# PROIECT_OPEN_READER_v56.net
KiCad netlist of a schematic drawn in EAGLE
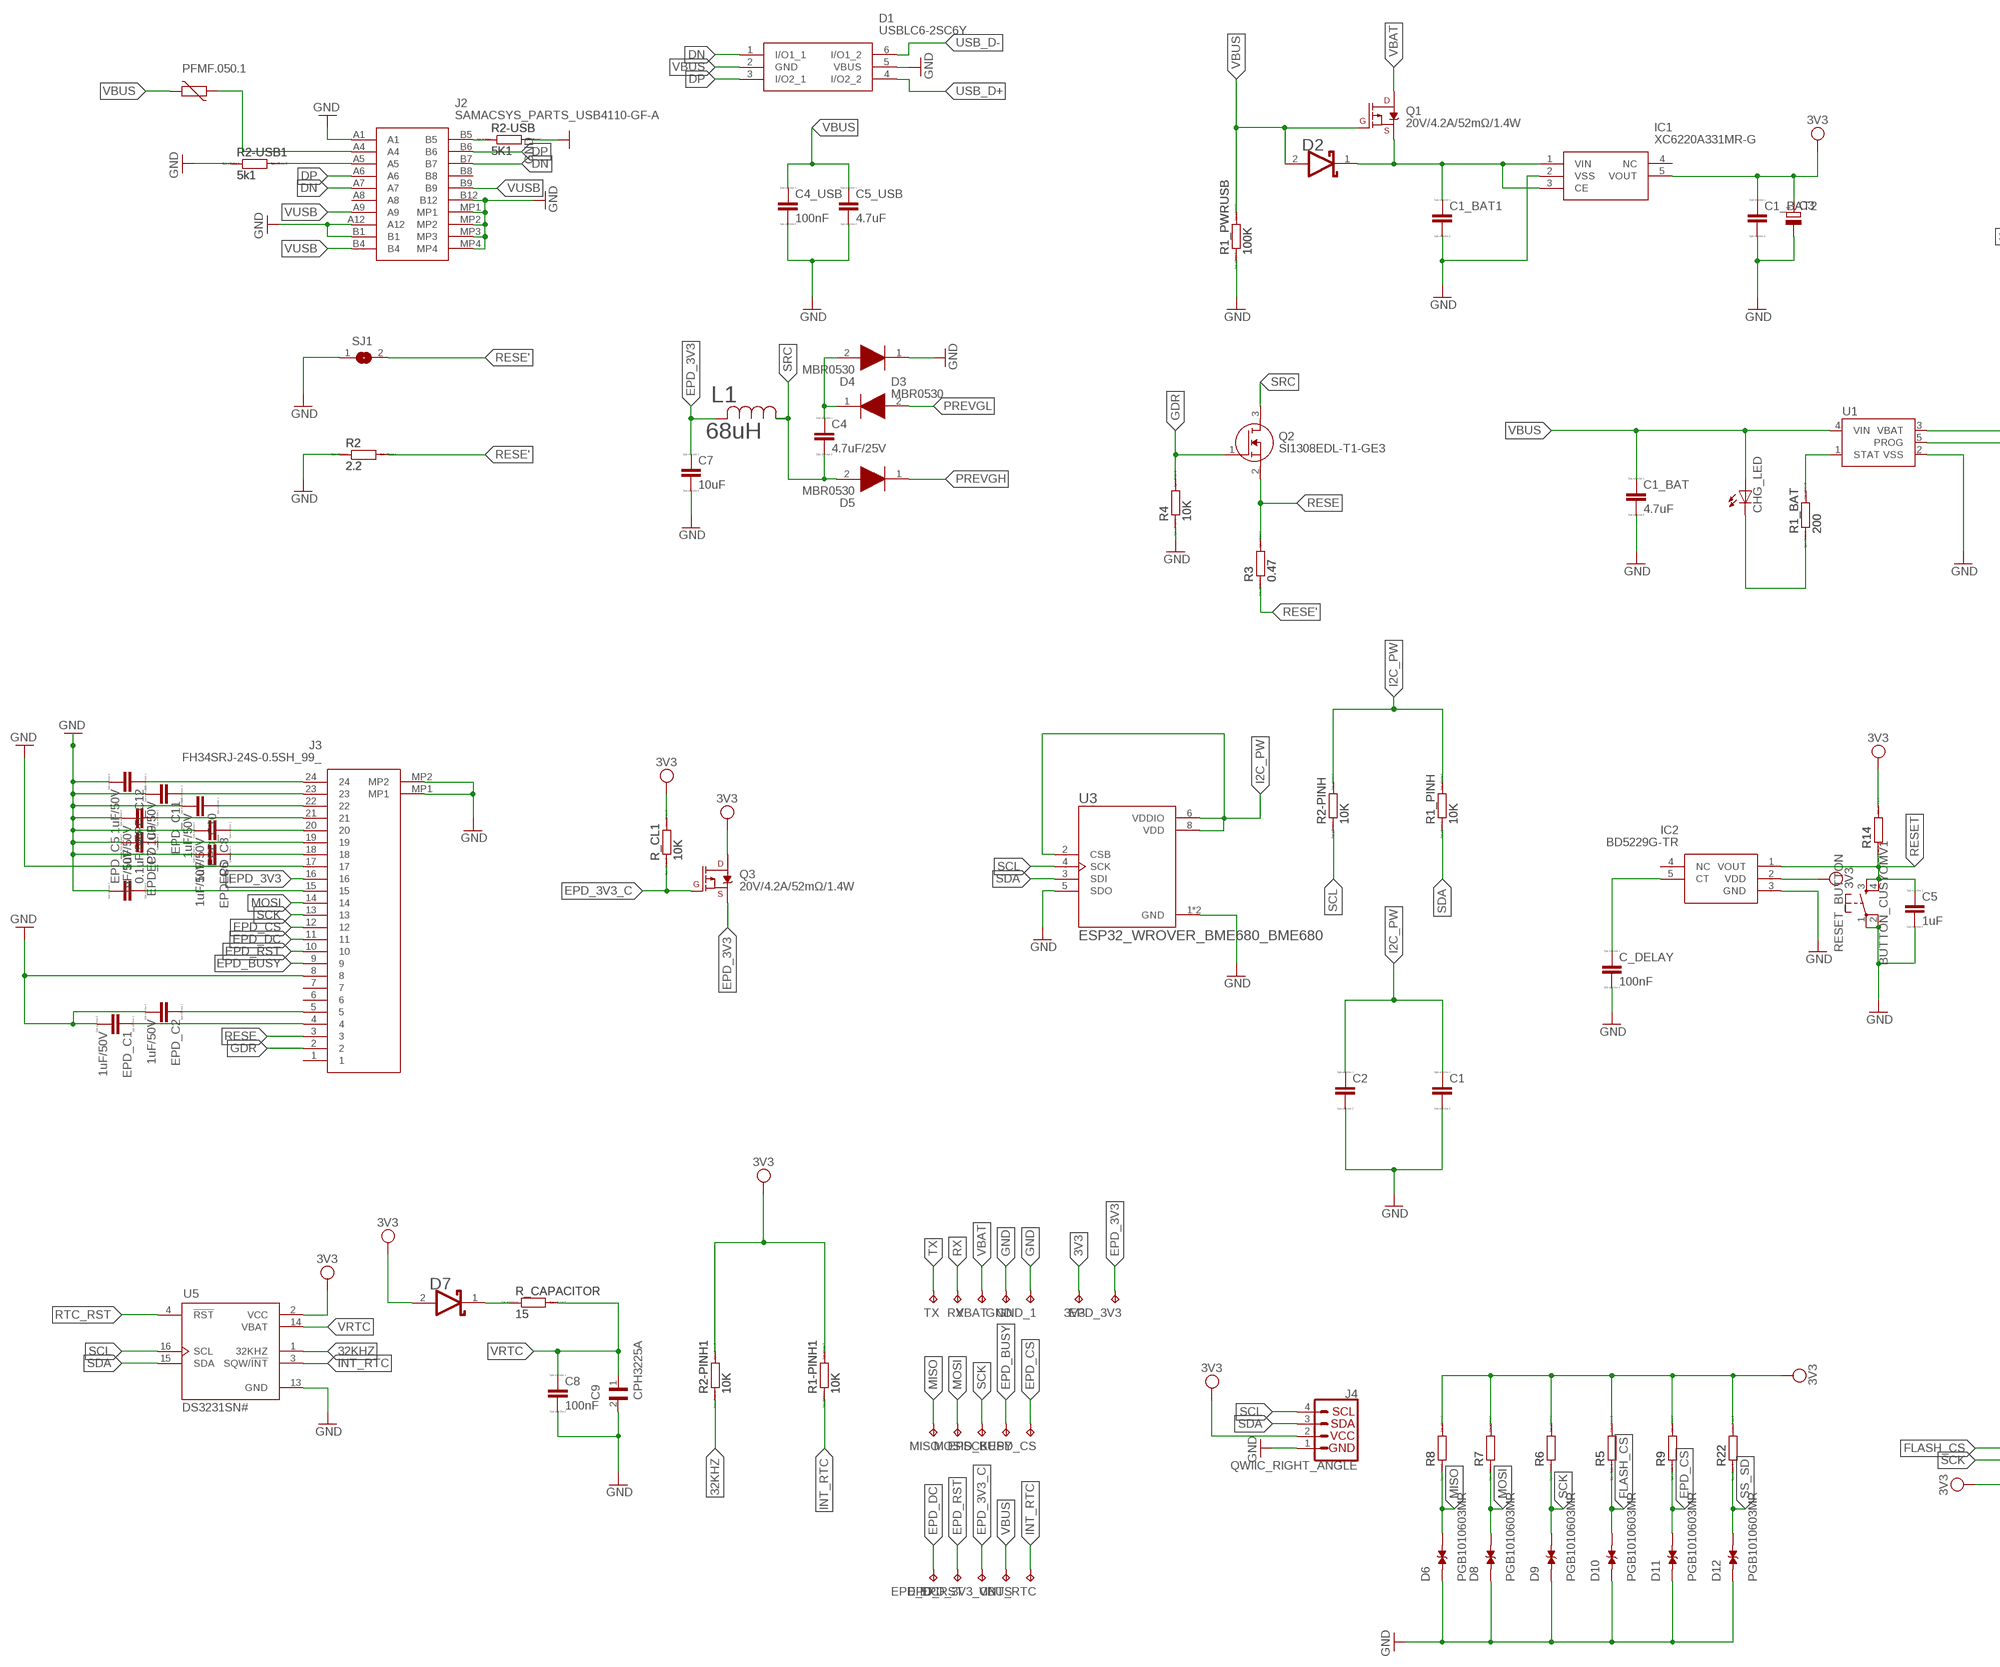
[diagram p0: schematic, sheet 1, part 1 of 2]
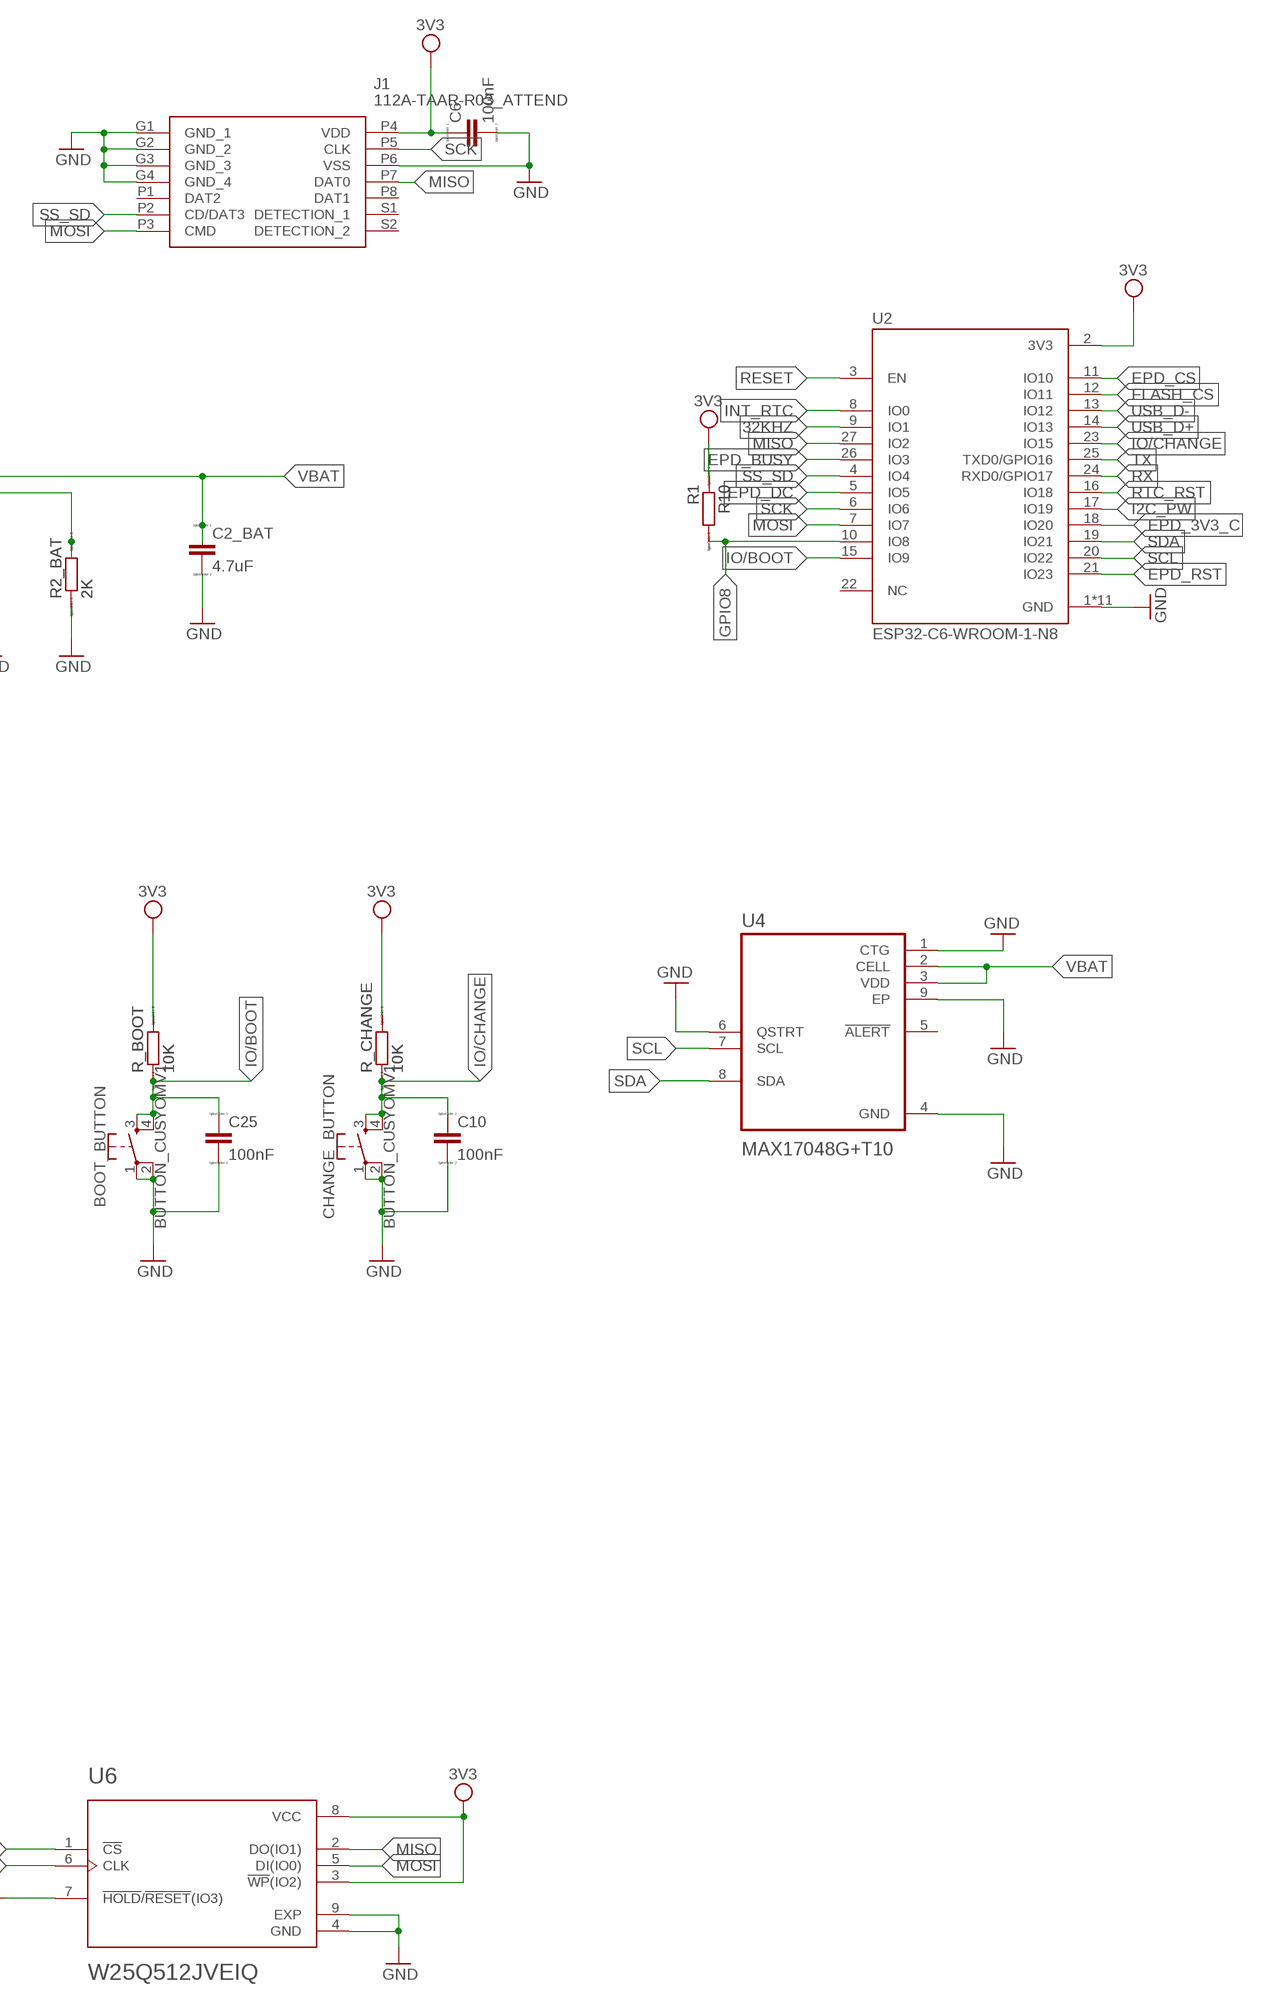
[diagram p1: schematic, sheet 1, part 2 of 2]

(export (version "E")
  (design (tool "Eeschema 10.0.6"))
  (components
    (comp (ref "3V3")
      (value "TPTP20R")
      (footprint "eagle-import:TP20R")
      (libsource (lib "eagle-import") (part "TPTP20R"))
    )
    (comp (ref "BOOT_BUTTON")
      (value "BUTTON_CUSYOMV1")
      (footprint "eagle-import:MYBUTTON")
      (libsource (lib "eagle-import") (part "BUTTON_CUSYOMV1"))
    )
    (comp (ref "C1")
      (value "EAGLE-LTSPICE_CC0402")
      (footprint "eagle-import:EAGLE-LTSPICE_C0402")
      (libsource (lib "eagle-import") (part "EAGLE-LTSPICE_CC0402"))
    )
    (comp (ref "C1_BAT")
      (value "4.7uF")
      (footprint "eagle-import:EAGLE-LTSPICE_C0402")
      (libsource (lib "eagle-import") (part "EAGLE-LTSPICE_CC0402"))
    )
    (comp (ref "C1_BAT1")
      (value "EAGLE-LTSPICE_CC0402")
      (footprint "eagle-import:EAGLE-LTSPICE_C0402")
      (libsource (lib "eagle-import") (part "EAGLE-LTSPICE_CC0402"))
    )
    (comp (ref "C1_BAT2")
      (value "EAGLE-LTSPICE_CC0402")
      (footprint "eagle-import:EAGLE-LTSPICE_C0402")
      (libsource (lib "eagle-import") (part "EAGLE-LTSPICE_CC0402"))
    )
    (comp (ref "C2")
      (value "EAGLE-LTSPICE_CC0402")
      (footprint "eagle-import:EAGLE-LTSPICE_C0402")
      (libsource (lib "eagle-import") (part "EAGLE-LTSPICE_CC0402"))
    )
    (comp (ref "C2_BAT")
      (value "4.7uF")
      (footprint "eagle-import:EAGLE-LTSPICE_C0402")
      (libsource (lib "eagle-import") (part "EAGLE-LTSPICE_CC0402"))
    )
    (comp (ref "C3")
      (value "RCL_CPOL-EUCT3528")
      (footprint "eagle-import:RCL_CT3528")
      (libsource (lib "eagle-import") (part "RCL_CPOL-EUCT3528"))
    )
    (comp (ref "C4")
      (value "4.7uF/25V")
      (footprint "eagle-import:EAGLE-LTSPICE_C0402")
      (libsource (lib "eagle-import") (part "EAGLE-LTSPICE_CC0402"))
    )
    (comp (ref "C4_USB")
      (value "100nF")
      (footprint "eagle-import:EAGLE-LTSPICE_C0402")
      (libsource (lib "eagle-import") (part "EAGLE-LTSPICE_CC0402"))
    )
    (comp (ref "C5")
      (value "1uF")
      (footprint "eagle-import:EAGLE-LTSPICE_C0402")
      (libsource (lib "eagle-import") (part "EAGLE-LTSPICE_CC0402"))
    )
    (comp (ref "C5_USB")
      (value "4.7uF")
      (footprint "eagle-import:EAGLE-LTSPICE_C0402")
      (libsource (lib "eagle-import") (part "EAGLE-LTSPICE_CC0402"))
    )
    (comp (ref "C6")
      (value "100nF")
      (footprint "eagle-import:EAGLE-LTSPICE_C0402")
      (libsource (lib "eagle-import") (part "EAGLE-LTSPICE_CC0402"))
    )
    (comp (ref "C7")
      (value "10uF")
      (footprint "eagle-import:EAGLE-LTSPICE_C0402")
      (libsource (lib "eagle-import") (part "EAGLE-LTSPICE_CC0402"))
    )
    (comp (ref "C8")
      (value "100nF")
      (footprint "eagle-import:EAGLE-LTSPICE_C0402")
      (libsource (lib "eagle-import") (part "EAGLE-LTSPICE_CC0402"))
    )
    (comp (ref "C9")
      (value "CPH3225A")
      (footprint "eagle-import:CAPCP3225X100N")
      (fields (field (name "MF") "Seiko Instruments"))
      (libsource (lib "eagle-import") (part "CPH3225A"))
    )
    (comp (ref "C10")
      (value "100nF")
      (footprint "eagle-import:EAGLE-LTSPICE_C0402")
      (libsource (lib "eagle-import") (part "EAGLE-LTSPICE_CC0402"))
    )
    (comp (ref "C25")
      (value "100nF")
      (footprint "eagle-import:EAGLE-LTSPICE_C0402")
      (libsource (lib "eagle-import") (part "EAGLE-LTSPICE_CC0402"))
    )
    (comp (ref "CHANGE_BUTTON")
      (value "BUTTON_CUSYOMV1")
      (footprint "eagle-import:MYBUTTON")
      (libsource (lib "eagle-import") (part "BUTTON_CUSYOMV1"))
    )
    (comp (ref "CHG_LED")
      (value "ADAFRUIT_LEDCHIP-LED0603")
      (footprint "eagle-import:ADAFRUIT_CHIP-LED0603")
      (libsource (lib "eagle-import") (part "ADAFRUIT_LEDCHIP-LED0603"))
    )
    (comp (ref "C_DELAY")
      (value "100nF")
      (footprint "eagle-import:EAGLE-LTSPICE_C0402")
      (libsource (lib "eagle-import") (part "EAGLE-LTSPICE_CC0402"))
    )
    (comp (ref "D1")
      (value "USBLC6-2SC6Y")
      (footprint "eagle-import:SOT95P280X145-6N")
      (fields (field (name "MF") "STMicroelectronics"))
      (libsource (lib "eagle-import") (part "USBLC6-2SC6Y"))
    )
    (comp (ref "D2")
      (value "ESP32_WROVER_AVX---SD0805S020S1R0_AVX_SD0805S020S1R0_0_0AVX_SD0805S020S1R0_0_0")
      (footprint "eagle-import:ESP32_WROVER_AVX---SD0805S020S1R0_AVX_SD0805S020S1R0_0")
      (fields
        (field (name "DIGIKEY_PART_NUMBER") "478-7800-1-ND")
        (field (name "MF") "AVX")
        (field (name "MOUSER_PART_NUMBER") "581-SD0805S020S1R0")
      )
      (libsource (lib "eagle-import") (part "ESP32_WROVER_AVX---SD0805S020S1R0_AVX_SD0805S020S1R0_0_0AVX_SD0805S020S1R0_0_0"))
    )
    (comp (ref "D3")
      (value "MBR0530")
      (footprint "eagle-import:SOD3716X135N")
      (fields (field (name "MF") "ON Semiconductor"))
      (libsource (lib "eagle-import") (part "MBR0530"))
    )
    (comp (ref "D4")
      (value "MBR0530")
      (footprint "eagle-import:SOD3716X135N")
      (fields (field (name "MF") "ON Semiconductor"))
      (libsource (lib "eagle-import") (part "MBR0530"))
    )
    (comp (ref "D5")
      (value "MBR0530")
      (footprint "eagle-import:SOD3716X135N")
      (fields (field (name "MF") "ON Semiconductor"))
      (libsource (lib "eagle-import") (part "MBR0530"))
    )
    (comp (ref "D6")
      (value "PGB1010603MR")
      (footprint "eagle-import:DIOC1608X36N")
      (fields (field (name "MF") "Littelfuse Inc."))
      (libsource (lib "eagle-import") (part "PGB1010603MR"))
    )
    (comp (ref "D7")
      (value "ESP32_WROVER_AVX---SD0805S020S1R0_AVX_SD0805S020S1R0_0_0AVX_SD0805S020S1R0_0_0")
      (footprint "eagle-import:ESP32_WROVER_AVX---SD0805S020S1R0_AVX_SD0805S020S1R0_0")
      (fields
        (field (name "DIGIKEY_PART_NUMBER") "478-7800-1-ND")
        (field (name "MF") "AVX")
        (field (name "MOUSER_PART_NUMBER") "581-SD0805S020S1R0")
      )
      (libsource (lib "eagle-import") (part "ESP32_WROVER_AVX---SD0805S020S1R0_AVX_SD0805S020S1R0_0_0AVX_SD0805S020S1R0_0_0"))
    )
    (comp (ref "D8")
      (value "PGB1010603MR")
      (footprint "eagle-import:DIOC1608X36N")
      (fields (field (name "MF") "Littelfuse Inc."))
      (libsource (lib "eagle-import") (part "PGB1010603MR"))
    )
    (comp (ref "D9")
      (value "PGB1010603MR")
      (footprint "eagle-import:DIOC1608X36N")
      (fields (field (name "MF") "Littelfuse Inc."))
      (libsource (lib "eagle-import") (part "PGB1010603MR"))
    )
    (comp (ref "D10")
      (value "PGB1010603MR")
      (footprint "eagle-import:DIOC1608X36N")
      (fields (field (name "MF") "Littelfuse Inc."))
      (libsource (lib "eagle-import") (part "PGB1010603MR"))
    )
    (comp (ref "D11")
      (value "PGB1010603MR")
      (footprint "eagle-import:DIOC1608X36N")
      (fields (field (name "MF") "Littelfuse Inc."))
      (libsource (lib "eagle-import") (part "PGB1010603MR"))
    )
    (comp (ref "D12")
      (value "PGB1010603MR")
      (footprint "eagle-import:DIOC1608X36N")
      (fields (field (name "MF") "Littelfuse Inc."))
      (libsource (lib "eagle-import") (part "PGB1010603MR"))
    )
    (comp (ref "EPD_3V3")
      (value "TPTP20R")
      (footprint "eagle-import:TP20R")
      (libsource (lib "eagle-import") (part "TPTP20R"))
    )
    (comp (ref "EPD_3V3_C")
      (value "TPTP20R")
      (footprint "eagle-import:TP20R")
      (libsource (lib "eagle-import") (part "TPTP20R"))
    )
    (comp (ref "EPD_BUSY")
      (value "TPTP20R")
      (footprint "eagle-import:TP20R")
      (libsource (lib "eagle-import") (part "TPTP20R"))
    )
    (comp (ref "EPD_C1")
      (value "1uF/50V")
      (footprint "eagle-import:EAGLE-LTSPICE_C0402")
      (libsource (lib "eagle-import") (part "EAGLE-LTSPICE_CC0402"))
    )
    (comp (ref "EPD_C2")
      (value "1uF/50V")
      (footprint "eagle-import:EAGLE-LTSPICE_C0402")
      (libsource (lib "eagle-import") (part "EAGLE-LTSPICE_CC0402"))
    )
    (comp (ref "EPD_C5")
      (value "0.1uF/50V")
      (footprint "eagle-import:EAGLE-LTSPICE_C0402")
      (libsource (lib "eagle-import") (part "EAGLE-LTSPICE_CC0402"))
    )
    (comp (ref "EPD_C6")
      (value "1uF/50V")
      (footprint "eagle-import:EAGLE-LTSPICE_C0402")
      (libsource (lib "eagle-import") (part "EAGLE-LTSPICE_CC0402"))
    )
    (comp (ref "EPD_C7")
      (value "1uF/50V")
      (footprint "eagle-import:EAGLE-LTSPICE_C0402")
      (libsource (lib "eagle-import") (part "EAGLE-LTSPICE_CC0402"))
    )
    (comp (ref "EPD_C8")
      (value "1uF/50V")
      (footprint "eagle-import:EAGLE-LTSPICE_C0402")
      (libsource (lib "eagle-import") (part "EAGLE-LTSPICE_CC0402"))
    )
    (comp (ref "EPD_C9")
      (value "1uF/50V")
      (footprint "eagle-import:EAGLE-LTSPICE_C0402")
      (libsource (lib "eagle-import") (part "EAGLE-LTSPICE_CC0402"))
    )
    (comp (ref "EPD_C10")
      (value "1uF/50V")
      (footprint "eagle-import:EAGLE-LTSPICE_C0402")
      (libsource (lib "eagle-import") (part "EAGLE-LTSPICE_CC0402"))
    )
    (comp (ref "EPD_C11")
      (value "1uF/50V")
      (footprint "eagle-import:EAGLE-LTSPICE_C0402")
      (libsource (lib "eagle-import") (part "EAGLE-LTSPICE_CC0402"))
    )
    (comp (ref "EPD_C12")
      (value "1uF/50V")
      (footprint "eagle-import:EAGLE-LTSPICE_C0402")
      (libsource (lib "eagle-import") (part "EAGLE-LTSPICE_CC0402"))
    )
    (comp (ref "EPD_CS")
      (value "TPTP20R")
      (footprint "eagle-import:TP20R")
      (libsource (lib "eagle-import") (part "TPTP20R"))
    )
    (comp (ref "EPD_DC")
      (value "TPTP20R")
      (footprint "eagle-import:TP20R")
      (libsource (lib "eagle-import") (part "TPTP20R"))
    )
    (comp (ref "EPD_RST")
      (value "TPTP20R")
      (footprint "eagle-import:TP20R")
      (libsource (lib "eagle-import") (part "TPTP20R"))
    )
    (comp (ref "GND")
      (value "TPTP20R")
      (footprint "eagle-import:TP20R")
      (libsource (lib "eagle-import") (part "TPTP20R"))
    )
    (comp (ref "GND_1")
      (value "TPTP20R")
      (footprint "eagle-import:TP20R")
      (libsource (lib "eagle-import") (part "TPTP20R"))
    )
    (comp (ref "IC1")
      (value "XC6220A331MR-G")
      (footprint "eagle-import:SOT95P280X120-5N")
      (fields (field (name "MOUSER_PART_NUMBER") "865-XC6220A331MR-G"))
      (libsource (lib "eagle-import") (part "XC6220A331MR-G"))
    )
    (comp (ref "IC2")
      (value "BD5229G-TR")
      (footprint "eagle-import:SOT95P280X125-5N")
      (fields (field (name "MOUSER_PART_NUMBER") "755-BD5229G-TR"))
      (libsource (lib "eagle-import") (part "BD5229G-TR"))
    )
    (comp (ref "INT_RTC")
      (value "TPTP20R")
      (footprint "eagle-import:TP20R")
      (libsource (lib "eagle-import") (part "TPTP20R"))
    )
    (comp (ref "J1")
      (value "112A-TAAR-R03_ATTEND")
      (footprint "eagle-import:112ATAARR03ATTEND")
      (fields (field (name "MANUFACTURER_PART_NUMBER") "112A-TAAR-R03 ATTEND"))
      (libsource (lib "eagle-import") (part "112A-TAAR-R03_ATTEND"))
    )
    (comp (ref "J2")
      (value "SAMACSYS_PARTS_USB4110-GF-A")
      (footprint "eagle-import:SAMACSYS_PARTS_USB4110GFA")
      (fields
        (field (name "MANUFACTURER_PART_NUMBER") "USB4110-GF-A")
        (field (name "MOUSER_PART_NUMBER") "640-USB4110-GF-A")
      )
      (libsource (lib "eagle-import") (part "SAMACSYS_PARTS_USB4110-GF-A"))
    )
    (comp (ref "J3")
      (value "FH34SRJ-24S-0.5SH_99_")
      (footprint "eagle-import:FH34SRJ24S05SH99")
      (fields
        (field (name "MANUFACTURER_PART_NUMBER") "FH34SRJ-24S-0.5SH(99)")
        (field (name "MOUSER_PART_NUMBER") "798-FH34SRJ24S05SH99")
      )
      (libsource (lib "eagle-import") (part "FH34SRJ-24S-0.5SH_99_"))
    )
    (comp (ref "J4")
      (value "QWIIC_RIGHT_ANGLE")
      (footprint "eagle-import:JST04_1MM_RA")
      (libsource (lib "eagle-import") (part "QWIIC_CONNECTORJS-1MM"))
    )
    (comp (ref "L1")
      (value "68uH")
      (footprint "eagle-import:IND_4828-WE-TPC_WRE")
      (fields
        (field (name "MANUFACTURER_PART_NUMBER") "744043680")
        (field (name "COPYRIGHT") "Copyright (C) 2024 Ultra Librarian. All rights reserved.")
      )
      (libsource (lib "eagle-import") (part "744043680IND_4828-WE-TPC_WRE"))
    )
    (comp (ref "MISO")
      (value "TPTP20R")
      (footprint "eagle-import:TP20R")
      (libsource (lib "eagle-import") (part "TPTP20R"))
    )
    (comp (ref "MOSI")
      (value "TPTP20R")
      (footprint "eagle-import:TP20R")
      (libsource (lib "eagle-import") (part "TPTP20R"))
    )
    (comp (ref "PFMF.050.1")
      (value "ESP32C6_VARISTORCN1812")
      (footprint "eagle-import:ESP32C6_VARISTOR_CT_CN1812")
      (libsource (lib "eagle-import") (part "ESP32C6_VARISTORCN1812"))
    )
    (comp (ref "Q1")
      (value "20V/4.2A/52mΩ/1.4W")
      (footprint "eagle-import:ESP32_WROVER_SPARKFUN-DISCRETESEMI_SOT23-3")
      (libsource (lib "eagle-import") (part "ESP32_WROVER_SPARKFUN-DISCRETESEMI_MOSFET_PCH-DMG2305UX-7"))
    )
    (comp (ref "Q2")
      (value "SI1308EDL-T1-GE3")
      (footprint "eagle-import:SOT65P210X110-3N")
      (fields (field (name "MF") "Vishay Siliconix"))
      (libsource (lib "eagle-import") (part "SI1308EDL-T1-GE3"))
    )
    (comp (ref "Q3")
      (value "20V/4.2A/52mΩ/1.4W")
      (footprint "eagle-import:ESP32_WROVER_SPARKFUN-DISCRETESEMI_SOT23-3")
      (libsource (lib "eagle-import") (part "ESP32_WROVER_SPARKFUN-DISCRETESEMI_MOSFET_PCH-DMG2305UX-7"))
    )
    (comp (ref "R1-PINH1")
      (value "10K")
      (footprint "eagle-import:ESP32_WROVER_EAGLE-LTSPICE_R0402")
      (libsource (lib "eagle-import") (part "ESP32_WROVER_EAGLE-LTSPICE_RR0402"))
    )
    (comp (ref "R1_BAT")
      (value "200")
      (footprint "eagle-import:ESP32_WROVER_EAGLE-LTSPICE_R0402")
      (libsource (lib "eagle-import") (part "ESP32_WROVER_EAGLE-LTSPICE_RR0402"))
    )
    (comp (ref "R1_PINH")
      (value "10K")
      (footprint "eagle-import:ESP32_WROVER_EAGLE-LTSPICE_R0402")
      (libsource (lib "eagle-import") (part "ESP32_WROVER_EAGLE-LTSPICE_RR0402"))
    )
    (comp (ref "R1_PWRUSB")
      (value "100K")
      (footprint "eagle-import:ESP32_WROVER_EAGLE-LTSPICE_R0402")
      (libsource (lib "eagle-import") (part "ESP32_WROVER_EAGLE-LTSPICE_RR0402"))
    )
    (comp (ref "R2")
      (value "2.2")
      (footprint "eagle-import:ESP32_WROVER_EAGLE-LTSPICE_R0402")
      (libsource (lib "eagle-import") (part "ESP32_WROVER_EAGLE-LTSPICE_RR0402"))
    )
    (comp (ref "R2-PINH")
      (value "10K")
      (footprint "eagle-import:ESP32_WROVER_EAGLE-LTSPICE_R0402")
      (libsource (lib "eagle-import") (part "ESP32_WROVER_EAGLE-LTSPICE_RR0402"))
    )
    (comp (ref "R2-PINH1")
      (value "10K")
      (footprint "eagle-import:ESP32_WROVER_EAGLE-LTSPICE_R0402")
      (libsource (lib "eagle-import") (part "ESP32_WROVER_EAGLE-LTSPICE_RR0402"))
    )
    (comp (ref "R2-USB")
      (value "5K1")
      (footprint "eagle-import:ESP32_WROVER_EAGLE-LTSPICE_R0402")
      (libsource (lib "eagle-import") (part "ESP32_WROVER_EAGLE-LTSPICE_RR0402"))
    )
    (comp (ref "R2-USB1")
      (value "5k1")
      (footprint "eagle-import:ESP32_WROVER_EAGLE-LTSPICE_R0402")
      (libsource (lib "eagle-import") (part "ESP32_WROVER_EAGLE-LTSPICE_RR0402"))
    )
    (comp (ref "R2_BAT")
      (value "2K")
      (footprint "eagle-import:ESP32_WROVER_EAGLE-LTSPICE_R0402")
      (libsource (lib "eagle-import") (part "ESP32_WROVER_EAGLE-LTSPICE_RR0402"))
    )
    (comp (ref "R3")
      (value "0.47")
      (footprint "eagle-import:ESP32_WROVER_EAGLE-LTSPICE_R0402")
      (libsource (lib "eagle-import") (part "ESP32_WROVER_EAGLE-LTSPICE_RR0402"))
    )
    (comp (ref "R4")
      (value "10K")
      (footprint "eagle-import:ESP32_WROVER_EAGLE-LTSPICE_R0402")
      (libsource (lib "eagle-import") (part "ESP32_WROVER_EAGLE-LTSPICE_RR0402"))
    )
    (comp (ref "R5")
      (value "ESP32_WROVER_EAGLE-LTSPICE_RR0402")
      (footprint "eagle-import:ESP32_WROVER_EAGLE-LTSPICE_R0402")
      (libsource (lib "eagle-import") (part "ESP32_WROVER_EAGLE-LTSPICE_RR0402"))
    )
    (comp (ref "R6")
      (value "ESP32_WROVER_EAGLE-LTSPICE_RR0402")
      (footprint "eagle-import:ESP32_WROVER_EAGLE-LTSPICE_R0402")
      (libsource (lib "eagle-import") (part "ESP32_WROVER_EAGLE-LTSPICE_RR0402"))
    )
    (comp (ref "R7")
      (value "ESP32_WROVER_EAGLE-LTSPICE_RR0402")
      (footprint "eagle-import:ESP32_WROVER_EAGLE-LTSPICE_R0402")
      (libsource (lib "eagle-import") (part "ESP32_WROVER_EAGLE-LTSPICE_RR0402"))
    )
    (comp (ref "R8")
      (value "ESP32_WROVER_EAGLE-LTSPICE_RR0402")
      (footprint "eagle-import:ESP32_WROVER_EAGLE-LTSPICE_R0402")
      (libsource (lib "eagle-import") (part "ESP32_WROVER_EAGLE-LTSPICE_RR0402"))
    )
    (comp (ref "R9")
      (value "ESP32_WROVER_EAGLE-LTSPICE_RR0402")
      (footprint "eagle-import:ESP32_WROVER_EAGLE-LTSPICE_R0402")
      (libsource (lib "eagle-import") (part "ESP32_WROVER_EAGLE-LTSPICE_RR0402"))
    )
    (comp (ref "R10")
      (value "R1")
      (footprint "eagle-import:ESP32_WROVER_EAGLE-LTSPICE_R0402")
      (libsource (lib "eagle-import") (part "ESP32_WROVER_EAGLE-LTSPICE_RR0402"))
    )
    (comp (ref "R14")
      (value "ESP32_WROVER_EAGLE-LTSPICE_RR0402")
      (footprint "eagle-import:ESP32_WROVER_EAGLE-LTSPICE_R0402")
      (libsource (lib "eagle-import") (part "ESP32_WROVER_EAGLE-LTSPICE_RR0402"))
    )
    (comp (ref "R22")
      (value "ESP32_WROVER_EAGLE-LTSPICE_RR0402")
      (footprint "eagle-import:ESP32_WROVER_EAGLE-LTSPICE_R0402")
      (libsource (lib "eagle-import") (part "ESP32_WROVER_EAGLE-LTSPICE_RR0402"))
    )
    (comp (ref "RESET_BUTTON")
      (value "BUTTON_CUSYOMV1")
      (footprint "eagle-import:MYBUTTON")
      (libsource (lib "eagle-import") (part "BUTTON_CUSYOMV1"))
    )
    (comp (ref "RX")
      (value "TPTP20R")
      (footprint "eagle-import:TP20R")
      (libsource (lib "eagle-import") (part "TPTP20R"))
    )
    (comp (ref "R_BOOT")
      (value "10K")
      (footprint "eagle-import:ESP32_WROVER_EAGLE-LTSPICE_R0402")
      (libsource (lib "eagle-import") (part "ESP32_WROVER_EAGLE-LTSPICE_RR0402"))
    )
    (comp (ref "R_CAPACITOR")
      (value "15")
      (footprint "eagle-import:ESP32_WROVER_EAGLE-LTSPICE_R0402")
      (libsource (lib "eagle-import") (part "ESP32_WROVER_EAGLE-LTSPICE_RR0402"))
    )
    (comp (ref "R_CHANGE")
      (value "10K")
      (footprint "eagle-import:ESP32_WROVER_EAGLE-LTSPICE_R0402")
      (libsource (lib "eagle-import") (part "ESP32_WROVER_EAGLE-LTSPICE_RR0402"))
    )
    (comp (ref "R_CL1")
      (value "10K")
      (footprint "eagle-import:ESP32_WROVER_EAGLE-LTSPICE_R0402")
      (libsource (lib "eagle-import") (part "ESP32_WROVER_EAGLE-LTSPICE_RR0402"))
    )
    (comp (ref "SCK")
      (value "TPTP20R")
      (footprint "eagle-import:TP20R")
      (libsource (lib "eagle-import") (part "TPTP20R"))
    )
    (comp (ref "SJ1") (value "SJ") (footprint "eagle-import:SJ") (libsource (lib "eagle-import") (part "SJ")))
    (comp (ref "TX")
      (value "TPTP20R")
      (footprint "eagle-import:TP20R")
      (libsource (lib "eagle-import") (part "TPTP20R"))
    )
    (comp (ref "U1")
      (value "ESP32_WROVER_SPARKFUN-IC-POWER_MCP73831")
      (footprint "eagle-import:ESP32_WROVER_SPARKFUN-IC-POWER_SOT23-5")
      (libsource (lib "eagle-import") (part "ESP32_WROVER_SPARKFUN-IC-POWER_MCP73831"))
    )
    (comp (ref "U2")
      (value "ESP32-C6-WROOM-1-N8")
      (footprint "eagle-import:XCVR_ESP32-C6-WROOM-1-N8")
      (fields (field (name "MF") "Espressif Systems"))
      (libsource (lib "eagle-import") (part "ESP32-C6-WROOM-1-N8"))
    )
    (comp (ref "U3")
      (value "ESP32_WROVER_BME680_BME680")
      (footprint "eagle-import:ESP32_WROVER_BME680_PSON80P300X300X100-8N")
      (fields (field (name "MF") "Bosch Sensortec") (field (name "MP") "BME680"))
      (libsource (lib "eagle-import") (part "ESP32_WROVER_BME680_BME680"))
    )
    (comp (ref "U4")
      (value "MAX17048G+T10")
      (footprint "eagle-import:SON50P200X200X80-9N")
      (fields (field (name "MF") "Analog Devices"))
      (libsource (lib "eagle-import") (part "MAX17048G+T10"))
    )
    (comp (ref "U5")
      (value "DS3231SN#")
      (footprint "eagle-import:SOIC127P1032X265-16N")
      (fields (field (name "MF") "Analog Devices"))
      (libsource (lib "eagle-import") (part "DS3231SN#"))
    )
    (comp (ref "U6")
      (value "W25Q512JVEIQ")
      (footprint "eagle-import:SON127P600X800X80-9N")
      (fields (field (name "MF") "Winbond Electronics"))
      (libsource (lib "eagle-import") (part "W25Q512JVEIQ"))
    )
    (comp (ref "VBAT")
      (value "TPTP20R")
      (footprint "eagle-import:TP20R")
      (libsource (lib "eagle-import") (part "TPTP20R"))
    )
    (comp (ref "VBUS")
      (value "TPTP20R")
      (footprint "eagle-import:TP20R")
      (libsource (lib "eagle-import") (part "TPTP20R"))
    )
  )
  (nets
    (net (code "1") (name "3V3") (class "Default")
      (node (ref "3V3") (pin "TP") (pinfunction "TP_TP") (pintype "input"))
      (node (ref "C1_BAT2") (pin "1") (pinfunction "1_1") (pintype "passive"))
      (node (ref "C3") (pin "+") (pinfunction "+_+") (pintype "passive"))
      (node (ref "C6") (pin "1") (pinfunction "1_1") (pintype "passive"))
      (node (ref "D7") (pin "2") (pinfunction "ANODE_2") (pintype "bidirectional"))
      (node (ref "IC1") (pin "5") (pinfunction "VOUT_5") (pintype "bidirectional"))
      (node (ref "IC2") (pin "2") (pinfunction "VDD_2") (pintype "bidirectional"))
      (node (ref "J1") (pin "P4") (pinfunction "VDD_P4") (pintype "bidirectional"))
      (node (ref "J4") (pin "2") (pinfunction "2_2") (pintype "power_in"))
      (node (ref "Q3") (pin "3") (pinfunction "D_3") (pintype "bidirectional"))
      (node (ref "R1-PINH1") (pin "2") (pinfunction "2_2") (pintype "passive"))
      (node (ref "R10") (pin "1") (pinfunction "1_1") (pintype "passive"))
      (node (ref "R14") (pin "2") (pinfunction "2_2") (pintype "passive"))
      (node (ref "R2-PINH1") (pin "2") (pinfunction "2_2") (pintype "passive"))
      (node (ref "R22") (pin "2") (pinfunction "2_2") (pintype "passive"))
      (node (ref "R5") (pin "2") (pinfunction "2_2") (pintype "passive"))
      (node (ref "R6") (pin "2") (pinfunction "2_2") (pintype "passive"))
      (node (ref "R7") (pin "2") (pinfunction "2_2") (pintype "passive"))
      (node (ref "R8") (pin "2") (pinfunction "2_2") (pintype "passive"))
      (node (ref "R9") (pin "2") (pinfunction "2_2") (pintype "passive"))
      (node (ref "R_BOOT") (pin "2") (pinfunction "2_2") (pintype "passive"))
      (node (ref "R_CHANGE") (pin "2") (pinfunction "2_2") (pintype "passive"))
      (node (ref "R_CL1") (pin "2") (pinfunction "2_2") (pintype "passive"))
      (node (ref "U2") (pin "2") (pinfunction "3V3_2") (pintype "power_in"))
      (node (ref "U5") (pin "2") (pinfunction "VCC_2") (pintype "power_in"))
      (node (ref "U6") (pin "3") (pinfunction "~{WP}(IO2)_3") (pintype "bidirectional"))
      (node (ref "U6") (pin "7") (pinfunction "~{HOLD}/~{RESET}(IO3)_7") (pintype "bidirectional"))
      (node (ref "U6") (pin "8") (pinfunction "VCC_8") (pintype "power_in"))
    )
    (net (code "2") (name "32KHZ") (class "Default")
      (node (ref "R2-PINH1") (pin "1") (pinfunction "1_1") (pintype "passive"))
      (node (ref "U2") (pin "9") (pinfunction "IO1_9") (pintype "bidirectional"))
      (node (ref "U5") (pin "1") (pinfunction "32KHZ_1") (pintype "output"))
    )
    (net (code "3") (name "DN") (class "Default")
      (node (ref "D1") (pin "1") (pinfunction "I/O1_1_1") (pintype "bidirectional"))
      (node (ref "J2") (pin "A7") (pinfunction "A7_A7") (pintype "bidirectional"))
      (node (ref "J2") (pin "B7") (pinfunction "B7_B7") (pintype "bidirectional"))
    )
    (net (code "4") (name "DP") (class "Default")
      (node (ref "D1") (pin "3") (pinfunction "I/O2_1_3") (pintype "bidirectional"))
      (node (ref "J2") (pin "A6") (pinfunction "A6_A6") (pintype "bidirectional"))
      (node (ref "J2") (pin "B6") (pinfunction "B6_B6") (pintype "bidirectional"))
    )
    (net (code "5") (name "EPD_3V3") (class "Default")
      (node (ref "C7") (pin "1") (pinfunction "1_1") (pintype "passive"))
      (node (ref "EPD_3V3") (pin "TP") (pinfunction "TP_TP") (pintype "input"))
      (node (ref "J3") (pin "16") (pinfunction "16_16") (pintype "bidirectional"))
      (node (ref "L1") (pin "2") (pinfunction "2_2") (pintype "passive"))
      (node (ref "Q3") (pin "2") (pinfunction "S_2") (pintype "bidirectional"))
    )
    (net (code "6") (name "EPD_3V3_C") (class "Default")
      (node (ref "EPD_3V3_C") (pin "TP") (pinfunction "TP_TP") (pintype "input"))
      (node (ref "Q3") (pin "1") (pinfunction "G_1") (pintype "bidirectional"))
      (node (ref "R_CL1") (pin "1") (pinfunction "1_1") (pintype "passive"))
      (node (ref "U2") (pin "18") (pinfunction "IO20_18") (pintype "bidirectional"))
    )
    (net (code "7") (name "EPD_BUSY") (class "Default")
      (node (ref "EPD_BUSY") (pin "TP") (pinfunction "TP_TP") (pintype "input"))
      (node (ref "J3") (pin "9") (pinfunction "9_9") (pintype "bidirectional"))
      (node (ref "U2") (pin "26") (pinfunction "IO3_26") (pintype "bidirectional"))
    )
    (net (code "8") (name "EPD_CS") (class "Default")
      (node (ref "D11") (pin "2") (pinfunction "2_2") (pintype "passive"))
      (node (ref "EPD_CS") (pin "TP") (pinfunction "TP_TP") (pintype "input"))
      (node (ref "J3") (pin "12") (pinfunction "12_12") (pintype "bidirectional"))
      (node (ref "R9") (pin "1") (pinfunction "1_1") (pintype "passive"))
      (node (ref "U2") (pin "11") (pinfunction "IO10_11") (pintype "bidirectional"))
    )
    (net (code "9") (name "EPD_DC") (class "Default")
      (node (ref "EPD_DC") (pin "TP") (pinfunction "TP_TP") (pintype "input"))
      (node (ref "J3") (pin "11") (pinfunction "11_11") (pintype "bidirectional"))
      (node (ref "U2") (pin "5") (pinfunction "IO5_5") (pintype "bidirectional"))
    )
    (net (code "10") (name "EPD_RST") (class "Default")
      (node (ref "EPD_RST") (pin "TP") (pinfunction "TP_TP") (pintype "input"))
      (node (ref "J3") (pin "10") (pinfunction "10_10") (pintype "bidirectional"))
      (node (ref "U2") (pin "21") (pinfunction "IO23_21") (pintype "bidirectional"))
    )
    (net (code "11") (name "FLASH_CS") (class "Default")
      (node (ref "D10") (pin "2") (pinfunction "2_2") (pintype "passive"))
      (node (ref "R5") (pin "1") (pinfunction "1_1") (pintype "passive"))
      (node (ref "U2") (pin "12") (pinfunction "IO11_12") (pintype "bidirectional"))
      (node (ref "U6") (pin "1") (pinfunction "~{CS}_1") (pintype "input"))
    )
    (net (code "12") (name "GDR") (class "Default")
      (node (ref "J3") (pin "2") (pinfunction "2_2") (pintype "bidirectional"))
      (node (ref "Q2") (pin "1") (pinfunction "G_1") (pintype "bidirectional"))
      (node (ref "R4") (pin "2") (pinfunction "2_2") (pintype "passive"))
    )
    (net (code "13") (name "GND") (class "Default")
      (node (ref "BOOT_BUTTON") (pin "1") (pinfunction "1_1") (pintype "passive"))
      (node (ref "BOOT_BUTTON") (pin "2") (pinfunction "2_2") (pintype "passive"))
      (node (ref "C1") (pin "2") (pinfunction "2_2") (pintype "passive"))
      (node (ref "C10") (pin "2") (pinfunction "2_2") (pintype "passive"))
      (node (ref "C1_BAT") (pin "2") (pinfunction "2_2") (pintype "passive"))
      (node (ref "C1_BAT1") (pin "2") (pinfunction "2_2") (pintype "passive"))
      (node (ref "C1_BAT2") (pin "2") (pinfunction "2_2") (pintype "passive"))
      (node (ref "C2") (pin "2") (pinfunction "2_2") (pintype "passive"))
      (node (ref "C25") (pin "2") (pinfunction "2_2") (pintype "passive"))
      (node (ref "C2_BAT") (pin "2") (pinfunction "2_2") (pintype "passive"))
      (node (ref "C3") (pin "-") (pinfunction "-_-") (pintype "passive"))
      (node (ref "C4_USB") (pin "2") (pinfunction "2_2") (pintype "passive"))
      (node (ref "C5") (pin "2") (pinfunction "2_2") (pintype "passive"))
      (node (ref "C5_USB") (pin "2") (pinfunction "2_2") (pintype "passive"))
      (node (ref "C6") (pin "2") (pinfunction "2_2") (pintype "passive"))
      (node (ref "C7") (pin "2") (pinfunction "2_2") (pintype "passive"))
      (node (ref "C8") (pin "2") (pinfunction "2_2") (pintype "passive"))
      (node (ref "C9") (pin "2") (pinfunction "2_2") (pintype "passive"))
      (node (ref "CHANGE_BUTTON") (pin "1") (pinfunction "1_1") (pintype "passive"))
      (node (ref "CHANGE_BUTTON") (pin "2") (pinfunction "2_2") (pintype "passive"))
      (node (ref "C_DELAY") (pin "2") (pinfunction "2_2") (pintype "passive"))
      (node (ref "D1") (pin "5") (pinfunction "VBUS_5") (pintype "bidirectional"))
      (node (ref "D10") (pin "1") (pinfunction "1_1") (pintype "passive"))
      (node (ref "D11") (pin "1") (pinfunction "1_1") (pintype "passive"))
      (node (ref "D12") (pin "1") (pinfunction "1_1") (pintype "passive"))
      (node (ref "D4") (pin "1") (pinfunction "K_1") (pintype "bidirectional"))
      (node (ref "D6") (pin "1") (pinfunction "1_1") (pintype "passive"))
      (node (ref "D8") (pin "1") (pinfunction "1_1") (pintype "passive"))
      (node (ref "D9") (pin "1") (pinfunction "1_1") (pintype "passive"))
      (node (ref "EPD_C1") (pin "2") (pinfunction "2_2") (pintype "passive"))
      (node (ref "EPD_C10") (pin "2") (pinfunction "2_2") (pintype "passive"))
      (node (ref "EPD_C11") (pin "2") (pinfunction "2_2") (pintype "passive"))
      (node (ref "EPD_C12") (pin "2") (pinfunction "2_2") (pintype "passive"))
      (node (ref "EPD_C2") (pin "2") (pinfunction "2_2") (pintype "passive"))
      (node (ref "EPD_C5") (pin "1") (pinfunction "1_1") (pintype "passive"))
      (node (ref "EPD_C6") (pin "2") (pinfunction "2_2") (pintype "passive"))
      (node (ref "EPD_C7") (pin "2") (pinfunction "2_2") (pintype "passive"))
      (node (ref "EPD_C8") (pin "2") (pinfunction "2_2") (pintype "passive"))
      (node (ref "EPD_C9") (pin "2") (pinfunction "2_2") (pintype "passive"))
      (node (ref "GND") (pin "TP") (pinfunction "TP_TP") (pintype "input"))
      (node (ref "GND_1") (pin "TP") (pinfunction "TP_TP") (pintype "input"))
      (node (ref "IC1") (pin "2") (pinfunction "VSS_2") (pintype "bidirectional"))
      (node (ref "IC2") (pin "3") (pinfunction "GND_3") (pintype "bidirectional"))
      (node (ref "J1") (pin "G1") (pinfunction "GND_1_G1") (pintype "bidirectional"))
      (node (ref "J1") (pin "G2") (pinfunction "GND_2_G2") (pintype "bidirectional"))
      (node (ref "J1") (pin "G3") (pinfunction "GND_3_G3") (pintype "bidirectional"))
      (node (ref "J1") (pin "G4") (pinfunction "GND_4_G4") (pintype "bidirectional"))
      (node (ref "J1") (pin "P6") (pinfunction "VSS_P6") (pintype "bidirectional"))
      (node (ref "J2") (pin "A1") (pinfunction "A1_A1") (pintype "bidirectional"))
      (node (ref "J2") (pin "A12") (pinfunction "A12_A12") (pintype "bidirectional"))
      (node (ref "J2") (pin "B1") (pinfunction "B1_B1") (pintype "bidirectional"))
      (node (ref "J2") (pin "B12") (pinfunction "B12_B12") (pintype "bidirectional"))
      (node (ref "J2") (pin "MP1") (pinfunction "MP1_MP1") (pintype "bidirectional"))
      (node (ref "J2") (pin "MP2") (pinfunction "MP2_MP2") (pintype "bidirectional"))
      (node (ref "J2") (pin "MP3") (pinfunction "MP3_MP3") (pintype "bidirectional"))
      (node (ref "J2") (pin "MP4") (pinfunction "MP4_MP4") (pintype "bidirectional"))
      (node (ref "J3") (pin "17") (pinfunction "17_17") (pintype "bidirectional"))
      (node (ref "J3") (pin "8") (pinfunction "8_8") (pintype "bidirectional"))
      (node (ref "J3") (pin "MP1") (pinfunction "MP1_MP1") (pintype "bidirectional"))
      (node (ref "J3") (pin "MP2") (pinfunction "MP2_MP2") (pintype "bidirectional"))
      (node (ref "J4") (pin "1") (pinfunction "1_1") (pintype "power_in"))
      (node (ref "R1_PWRUSB") (pin "1") (pinfunction "1_1") (pintype "passive"))
      (node (ref "R2") (pin "1") (pinfunction "1_1") (pintype "passive"))
      (node (ref "R2-USB") (pin "2") (pinfunction "2_2") (pintype "passive"))
      (node (ref "R2-USB1") (pin "1") (pinfunction "1_1") (pintype "passive"))
      (node (ref "R2_BAT") (pin "1") (pinfunction "1_1") (pintype "passive"))
      (node (ref "R4") (pin "1") (pinfunction "1_1") (pintype "passive"))
      (node (ref "RESET_BUTTON") (pin "1") (pinfunction "1_1") (pintype "passive"))
      (node (ref "RESET_BUTTON") (pin "2") (pinfunction "2_2") (pintype "passive"))
      (node (ref "SJ1") (pin "1") (pinfunction "1_1") (pintype "passive"))
      (node (ref "U1") (pin "2") (pinfunction "VSS_2") (pintype "power_in"))
      (node (ref "U2") (pin "1") (pinfunction "GND_1") (pintype "power_in"))
      (node (ref "U2") (pin "28") (pinfunction "GND_28") (pintype "power_in"))
      (node (ref "U2") (pin "29_1") (pinfunction "GND_29_1") (pintype "power_in"))
      (node (ref "U2") (pin "29_2") (pinfunction "GND_29_2") (pintype "power_in"))
      (node (ref "U2") (pin "29_3") (pinfunction "GND_29_3") (pintype "power_in"))
      (node (ref "U2") (pin "29_4") (pinfunction "GND_29_4") (pintype "power_in"))
      (node (ref "U2") (pin "29_5") (pinfunction "GND_29_5") (pintype "power_in"))
      (node (ref "U2") (pin "29_6") (pinfunction "GND_29_6") (pintype "power_in"))
      (node (ref "U2") (pin "29_7") (pinfunction "GND_29_7") (pintype "power_in"))
      (node (ref "U2") (pin "29_8") (pinfunction "GND_29_8") (pintype "power_in"))
      (node (ref "U2") (pin "29_9") (pinfunction "GND_29_9") (pintype "power_in"))
      (node (ref "U3") (pin "1") (pinfunction "GND_1") (pintype "power_in"))
      (node (ref "U3") (pin "5") (pinfunction "SDO_5") (pintype "bidirectional"))
      (node (ref "U3") (pin "7") (pinfunction "GND_7") (pintype "power_in"))
      (node (ref "U4") (pin "1") (pinfunction "CTG_1") (pintype "power_in"))
      (node (ref "U4") (pin "4") (pinfunction "GND_4") (pintype "power_in"))
      (node (ref "U4") (pin "6") (pinfunction "QSTRT_6") (pintype "input"))
      (node (ref "U4") (pin "9") (pinfunction "EP_9") (pintype "power_in"))
      (node (ref "U5") (pin "13") (pinfunction "GND_13") (pintype "power_in"))
      (node (ref "U6") (pin "4") (pinfunction "GND_4") (pintype "power_in"))
      (node (ref "U6") (pin "9") (pinfunction "EXP_9") (pintype "passive"))
    )
    (net (code "14") (name "GPIO8") (class "Default")
      (node (ref "R10") (pin "2") (pinfunction "2_2") (pintype "passive"))
      (node (ref "U2") (pin "10") (pinfunction "IO8_10") (pintype "bidirectional"))
    )
    (net (code "15") (name "I2C_PW") (class "Default")
      (node (ref "C1") (pin "1") (pinfunction "1_1") (pintype "passive"))
      (node (ref "C2") (pin "1") (pinfunction "1_1") (pintype "passive"))
      (node (ref "R1_PINH") (pin "2") (pinfunction "2_2") (pintype "passive"))
      (node (ref "R2-PINH") (pin "2") (pinfunction "2_2") (pintype "passive"))
      (node (ref "U2") (pin "17") (pinfunction "IO19_17") (pintype "bidirectional"))
      (node (ref "U3") (pin "2") (pinfunction "CSB_2") (pintype "input"))
      (node (ref "U3") (pin "6") (pinfunction "VDDIO_6") (pintype "power_in"))
      (node (ref "U3") (pin "8") (pinfunction "VDD_8") (pintype "power_in"))
    )
    (net (code "16") (name "INT_RTC") (class "Default")
      (node (ref "INT_RTC") (pin "TP") (pinfunction "TP_TP") (pintype "input"))
      (node (ref "R1-PINH1") (pin "1") (pinfunction "1_1") (pintype "passive"))
      (node (ref "U2") (pin "8") (pinfunction "IO0_8") (pintype "bidirectional"))
      (node (ref "U5") (pin "3") (pinfunction "SQW/~{INT}_3") (pintype "output"))
    )
    (net (code "17") (name "IO{slash}BOOT") (class "Default")
      (node (ref "BOOT_BUTTON") (pin "3") (pinfunction "3_3") (pintype "passive"))
      (node (ref "BOOT_BUTTON") (pin "4") (pinfunction "4_4") (pintype "passive"))
      (node (ref "C25") (pin "1") (pinfunction "1_1") (pintype "passive"))
      (node (ref "R_BOOT") (pin "1") (pinfunction "1_1") (pintype "passive"))
      (node (ref "U2") (pin "15") (pinfunction "IO9_15") (pintype "bidirectional"))
    )
    (net (code "18") (name "IO{slash}CHANGE") (class "Default")
      (node (ref "C10") (pin "1") (pinfunction "1_1") (pintype "passive"))
      (node (ref "CHANGE_BUTTON") (pin "3") (pinfunction "3_3") (pintype "passive"))
      (node (ref "CHANGE_BUTTON") (pin "4") (pinfunction "4_4") (pintype "passive"))
      (node (ref "R_CHANGE") (pin "1") (pinfunction "1_1") (pintype "passive"))
      (node (ref "U2") (pin "23") (pinfunction "IO15_23") (pintype "bidirectional"))
    )
    (net (code "19") (name "MISO") (class "Default")
      (node (ref "D6") (pin "2") (pinfunction "2_2") (pintype "passive"))
      (node (ref "J1") (pin "P7") (pinfunction "DAT0_P7") (pintype "bidirectional"))
      (node (ref "MISO") (pin "TP") (pinfunction "TP_TP") (pintype "input"))
      (node (ref "R8") (pin "1") (pinfunction "1_1") (pintype "passive"))
      (node (ref "U2") (pin "27") (pinfunction "IO2_27") (pintype "bidirectional"))
      (node (ref "U6") (pin "2") (pinfunction "DO(IO1)_2") (pintype "bidirectional"))
    )
    (net (code "20") (name "MOSI") (class "Default")
      (node (ref "D8") (pin "2") (pinfunction "2_2") (pintype "passive"))
      (node (ref "J1") (pin "P3") (pinfunction "CMD_P3") (pintype "bidirectional"))
      (node (ref "J3") (pin "14") (pinfunction "14_14") (pintype "bidirectional"))
      (node (ref "MOSI") (pin "TP") (pinfunction "TP_TP") (pintype "input"))
      (node (ref "R7") (pin "1") (pinfunction "1_1") (pintype "passive"))
      (node (ref "U2") (pin "7") (pinfunction "IO7_7") (pintype "bidirectional"))
      (node (ref "U6") (pin "5") (pinfunction "DI(IO0)_5") (pintype "bidirectional"))
    )
    (net (code "21") (name "Net-(CHG_LED-PadC)") (class "Default")
      (node (ref "CHG_LED") (pin "C") (pinfunction "C_C") (pintype "passive"))
      (node (ref "R1_BAT") (pin "1") (pinfunction "1_1") (pintype "passive"))
    )
    (net (code "22") (name "Net-(D2-CATHODE)") (class "Default")
      (node (ref "C1_BAT1") (pin "1") (pinfunction "1_1") (pintype "passive"))
      (node (ref "D2") (pin "1") (pinfunction "CATHODE_1") (pintype "bidirectional"))
      (node (ref "IC1") (pin "1") (pinfunction "VIN_1") (pintype "bidirectional"))
      (node (ref "IC1") (pin "3") (pinfunction "CE_3") (pintype "bidirectional"))
      (node (ref "Q1") (pin "2") (pinfunction "S_2") (pintype "bidirectional"))
    )
    (net (code "23") (name "Net-(D3-K)") (class "Default")
      (node (ref "C4") (pin "1") (pinfunction "1_1") (pintype "passive"))
      (node (ref "D3") (pin "1") (pinfunction "K_1") (pintype "bidirectional"))
      (node (ref "D4") (pin "2") (pinfunction "A_2") (pintype "bidirectional"))
    )
    (net (code "24") (name "Net-(D7-CATHODE)") (class "Default")
      (node (ref "D7") (pin "1") (pinfunction "CATHODE_1") (pintype "bidirectional"))
      (node (ref "R_CAPACITOR") (pin "1") (pinfunction "1_1") (pintype "passive"))
    )
    (net (code "25") (name "Net-(EPD_C1-Pad1)") (class "Default")
      (node (ref "EPD_C1") (pin "1") (pinfunction "1_1") (pintype "passive"))
      (node (ref "J3") (pin "4") (pinfunction "4_4") (pintype "bidirectional"))
    )
    (net (code "26") (name "Net-(EPD_C2-Pad1)") (class "Default")
      (node (ref "EPD_C2") (pin "1") (pinfunction "1_1") (pintype "passive"))
      (node (ref "J3") (pin "5") (pinfunction "5_5") (pintype "bidirectional"))
    )
    (net (code "27") (name "Net-(EPD_C5-Pad2)") (class "Default")
      (node (ref "EPD_C5") (pin "2") (pinfunction "2_2") (pintype "passive"))
      (node (ref "J3") (pin "15") (pinfunction "15_15") (pintype "bidirectional"))
    )
    (net (code "28") (name "Net-(EPD_C6-Pad1)") (class "Default")
      (node (ref "EPD_C6") (pin "1") (pinfunction "1_1") (pintype "passive"))
      (node (ref "J3") (pin "18") (pinfunction "18_18") (pintype "bidirectional"))
    )
    (net (code "29") (name "Net-(EPD_C7-Pad1)") (class "Default")
      (node (ref "EPD_C7") (pin "1") (pinfunction "1_1") (pintype "passive"))
      (node (ref "J3") (pin "19") (pinfunction "19_19") (pintype "bidirectional"))
    )
    (net (code "30") (name "Net-(EPD_C8-Pad1)") (class "Default")
      (node (ref "EPD_C8") (pin "1") (pinfunction "1_1") (pintype "passive"))
      (node (ref "J3") (pin "20") (pinfunction "20_20") (pintype "bidirectional"))
    )
    (net (code "31") (name "Net-(EPD_C9-Pad1)") (class "Default")
      (node (ref "EPD_C9") (pin "1") (pinfunction "1_1") (pintype "passive"))
      (node (ref "J3") (pin "21") (pinfunction "21_21") (pintype "bidirectional"))
    )
    (net (code "32") (name "Net-(EPD_C10-Pad1)") (class "Default")
      (node (ref "EPD_C10") (pin "1") (pinfunction "1_1") (pintype "passive"))
      (node (ref "J3") (pin "22") (pinfunction "22_22") (pintype "bidirectional"))
    )
    (net (code "33") (name "Net-(EPD_C11-Pad1)") (class "Default")
      (node (ref "EPD_C11") (pin "1") (pinfunction "1_1") (pintype "passive"))
      (node (ref "J3") (pin "23") (pinfunction "23_23") (pintype "bidirectional"))
    )
    (net (code "34") (name "Net-(EPD_C12-Pad1)") (class "Default")
      (node (ref "EPD_C12") (pin "1") (pinfunction "1_1") (pintype "passive"))
      (node (ref "J3") (pin "24") (pinfunction "24_24") (pintype "bidirectional"))
    )
    (net (code "35") (name "Net-(IC2-CT)") (class "Default")
      (node (ref "C_DELAY") (pin "1") (pinfunction "1_1") (pintype "passive"))
      (node (ref "IC2") (pin "5") (pinfunction "CT_5") (pintype "bidirectional"))
    )
    (net (code "36") (name "Net-(J2-PadA4)") (class "Default")
      (node (ref "J2") (pin "A4") (pinfunction "A4_A4") (pintype "bidirectional"))
      (node (ref "PFMF.050.1") (pin "1") (pinfunction "1_1") (pintype "passive"))
    )
    (net (code "37") (name "Net-(J2-PadA5)") (class "Default")
      (node (ref "J2") (pin "A5") (pinfunction "A5_A5") (pintype "bidirectional"))
      (node (ref "R2-USB1") (pin "2") (pinfunction "2_2") (pintype "passive"))
    )
    (net (code "38") (name "Net-(J2-PadB5)") (class "Default")
      (node (ref "J2") (pin "B5") (pinfunction "B5_B5") (pintype "bidirectional"))
      (node (ref "R2-USB") (pin "1") (pinfunction "1_1") (pintype "passive"))
    )
    (net (code "39") (name "Net-(U1-PROG)") (class "Default")
      (node (ref "R2_BAT") (pin "2") (pinfunction "2_2") (pintype "passive"))
      (node (ref "U1") (pin "5") (pinfunction "PROG_5") (pintype "input"))
    )
    (net (code "40") (name "Net-(U1-STAT)") (class "Default")
      (node (ref "R1_BAT") (pin "2") (pinfunction "2_2") (pintype "passive"))
      (node (ref "U1") (pin "1") (pinfunction "STAT_1") (pintype "output"))
    )
    (net (code "41") (name "PREVGH") (class "Default")
      (node (ref "D5") (pin "1") (pinfunction "K_1") (pintype "bidirectional"))
    )
    (net (code "42") (name "PREVGL") (class "Default")
      (node (ref "D3") (pin "2") (pinfunction "A_2") (pintype "bidirectional"))
    )
    (net (code "43") (name "RESE") (class "Default")
      (node (ref "J3") (pin "3") (pinfunction "3_3") (pintype "bidirectional"))
      (node (ref "Q2") (pin "2") (pinfunction "S_2") (pintype "bidirectional"))
      (node (ref "R3") (pin "2") (pinfunction "2_2") (pintype "passive"))
    )
    (net (code "44") (name "RESE'") (class "Default")
      (node (ref "R2") (pin "2") (pinfunction "2_2") (pintype "passive"))
      (node (ref "R3") (pin "1") (pinfunction "1_1") (pintype "passive"))
      (node (ref "SJ1") (pin "2") (pinfunction "2_2") (pintype "passive"))
    )
    (net (code "45") (name "RESET") (class "Default")
      (node (ref "C5") (pin "1") (pinfunction "1_1") (pintype "passive"))
      (node (ref "IC2") (pin "1") (pinfunction "VOUT_1") (pintype "bidirectional"))
      (node (ref "R14") (pin "1") (pinfunction "1_1") (pintype "passive"))
      (node (ref "RESET_BUTTON") (pin "3") (pinfunction "3_3") (pintype "passive"))
      (node (ref "RESET_BUTTON") (pin "4") (pinfunction "4_4") (pintype "passive"))
      (node (ref "U2") (pin "3") (pinfunction "EN_3") (pintype "input"))
    )
    (net (code "46") (name "RTC_RST") (class "Default")
      (node (ref "U2") (pin "16") (pinfunction "IO18_16") (pintype "bidirectional"))
      (node (ref "U5") (pin "4") (pinfunction "~{RST}_4") (pintype "input"))
    )
    (net (code "47") (name "RX") (class "Default")
      (node (ref "RX") (pin "TP") (pinfunction "TP_TP") (pintype "input"))
      (node (ref "U2") (pin "24") (pinfunction "RXD0/GPIO17_24") (pintype "bidirectional"))
    )
    (net (code "48") (name "SCK") (class "Default")
      (node (ref "D9") (pin "2") (pinfunction "2_2") (pintype "passive"))
      (node (ref "J1") (pin "P5") (pinfunction "CLK_P5") (pintype "bidirectional"))
      (node (ref "J3") (pin "13") (pinfunction "13_13") (pintype "bidirectional"))
      (node (ref "R6") (pin "1") (pinfunction "1_1") (pintype "passive"))
      (node (ref "SCK") (pin "TP") (pinfunction "TP_TP") (pintype "input"))
      (node (ref "U2") (pin "6") (pinfunction "IO6_6") (pintype "bidirectional"))
      (node (ref "U6") (pin "6") (pinfunction "CLK_6") (pintype "input"))
    )
    (net (code "49") (name "SCL") (class "Default")
      (node (ref "J4") (pin "4") (pinfunction "4_4") (pintype "passive"))
      (node (ref "R2-PINH") (pin "1") (pinfunction "1_1") (pintype "passive"))
      (node (ref "U2") (pin "20") (pinfunction "IO22_20") (pintype "bidirectional"))
      (node (ref "U3") (pin "4") (pinfunction "SCK_4") (pintype "input"))
      (node (ref "U4") (pin "7") (pinfunction "SCL_7") (pintype "input"))
      (node (ref "U5") (pin "16") (pinfunction "SCL_16") (pintype "input"))
    )
    (net (code "50") (name "SDA") (class "Default")
      (node (ref "J4") (pin "3") (pinfunction "3_3") (pintype "passive"))
      (node (ref "R1_PINH") (pin "1") (pinfunction "1_1") (pintype "passive"))
      (node (ref "U2") (pin "19") (pinfunction "IO21_19") (pintype "bidirectional"))
      (node (ref "U3") (pin "3") (pinfunction "SDI_3") (pintype "bidirectional"))
      (node (ref "U4") (pin "8") (pinfunction "SDA_8") (pintype "bidirectional"))
      (node (ref "U5") (pin "15") (pinfunction "SDA_15") (pintype "bidirectional"))
    )
    (net (code "51") (name "SRC") (class "Default")
      (node (ref "C4") (pin "2") (pinfunction "2_2") (pintype "passive"))
      (node (ref "D5") (pin "2") (pinfunction "A_2") (pintype "bidirectional"))
      (node (ref "L1") (pin "1") (pinfunction "1_1") (pintype "passive"))
      (node (ref "Q2") (pin "3") (pinfunction "D_3") (pintype "bidirectional"))
    )
    (net (code "52") (name "SS_SD") (class "Default")
      (node (ref "D12") (pin "2") (pinfunction "2_2") (pintype "passive"))
      (node (ref "J1") (pin "P2") (pinfunction "CD/DAT3_P2") (pintype "bidirectional"))
      (node (ref "R22") (pin "1") (pinfunction "1_1") (pintype "passive"))
      (node (ref "U2") (pin "4") (pinfunction "IO4_4") (pintype "bidirectional"))
    )
    (net (code "53") (name "TX") (class "Default")
      (node (ref "TX") (pin "TP") (pinfunction "TP_TP") (pintype "input"))
      (node (ref "U2") (pin "25") (pinfunction "TXD0/GPIO16_25") (pintype "bidirectional"))
    )
    (net (code "54") (name "USB_D+") (class "Default")
      (node (ref "D1") (pin "4") (pinfunction "I/O2_2_4") (pintype "bidirectional"))
      (node (ref "U2") (pin "14") (pinfunction "IO13_14") (pintype "bidirectional"))
    )
    (net (code "55") (name "USB_D-") (class "Default")
      (node (ref "D1") (pin "6") (pinfunction "I/O1_2_6") (pintype "bidirectional"))
      (node (ref "U2") (pin "13") (pinfunction "IO12_13") (pintype "bidirectional"))
    )
    (net (code "56") (name "VBAT") (class "Default")
      (node (ref "C2_BAT") (pin "1") (pinfunction "1_1") (pintype "passive"))
      (node (ref "Q1") (pin "3") (pinfunction "D_3") (pintype "bidirectional"))
      (node (ref "U1") (pin "3") (pinfunction "VBAT_3") (pintype "power_in"))
      (node (ref "U4") (pin "2") (pinfunction "CELL_2") (pintype "power_in"))
      (node (ref "U4") (pin "3") (pinfunction "VDD_3") (pintype "power_in"))
      (node (ref "VBAT") (pin "TP") (pinfunction "TP_TP") (pintype "input"))
    )
    (net (code "57") (name "VBUS") (class "Default")
      (node (ref "C1_BAT") (pin "1") (pinfunction "1_1") (pintype "passive"))
      (node (ref "C4_USB") (pin "1") (pinfunction "1_1") (pintype "passive"))
      (node (ref "C5_USB") (pin "1") (pinfunction "1_1") (pintype "passive"))
      (node (ref "CHG_LED") (pin "A") (pinfunction "A_A") (pintype "passive"))
      (node (ref "D1") (pin "2") (pinfunction "GND_2") (pintype "bidirectional"))
      (node (ref "D2") (pin "2") (pinfunction "ANODE_2") (pintype "bidirectional"))
      (node (ref "PFMF.050.1") (pin "2") (pinfunction "2_2") (pintype "passive"))
      (node (ref "Q1") (pin "1") (pinfunction "G_1") (pintype "bidirectional"))
      (node (ref "R1_PWRUSB") (pin "2") (pinfunction "2_2") (pintype "passive"))
      (node (ref "U1") (pin "4") (pinfunction "VIN_4") (pintype "power_in"))
      (node (ref "VBUS") (pin "TP") (pinfunction "TP_TP") (pintype "input"))
    )
    (net (code "58") (name "VRTC") (class "Default")
      (node (ref "C8") (pin "1") (pinfunction "1_1") (pintype "passive"))
      (node (ref "C9") (pin "1") (pinfunction "1_1") (pintype "passive"))
      (node (ref "R_CAPACITOR") (pin "2") (pinfunction "2_2") (pintype "passive"))
      (node (ref "U5") (pin "14") (pinfunction "VBAT_14") (pintype "power_in"))
    )
    (net (code "59") (name "VUSB") (class "Default")
      (node (ref "J2") (pin "A9") (pinfunction "A9_A9") (pintype "bidirectional"))
      (node (ref "J2") (pin "B4") (pinfunction "B4_B4") (pintype "bidirectional"))
      (node (ref "J2") (pin "B9") (pinfunction "B9_B9") (pintype "bidirectional"))
    )
    (net (code "60") (name "unconnected-(IC1-NC-Pad4)") (class "Default")
      (node (ref "IC1") (pin "4") (pinfunction "NC_4") (pintype "no_connect"))
    )
    (net (code "61") (name "unconnected-(IC2-NC-Pad4)") (class "Default")
      (node (ref "IC2") (pin "4") (pinfunction "NC_4") (pintype "no_connect"))
    )
    (net (code "62") (name "unconnected-(J1-DAT1-PadP8)") (class "Default")
      (node (ref "J1") (pin "P8") (pinfunction "DAT1_P8") (pintype "bidirectional"))
    )
    (net (code "63") (name "unconnected-(J1-DAT2-PadP1)") (class "Default")
      (node (ref "J1") (pin "P1") (pinfunction "DAT2_P1") (pintype "bidirectional"))
    )
    (net (code "64") (name "unconnected-(J1-DETECTION_1-PadS1)") (class "Default")
      (node (ref "J1") (pin "S1") (pinfunction "DETECTION_1_S1") (pintype "bidirectional"))
    )
    (net (code "65") (name "unconnected-(J1-DETECTION_2-PadS2)") (class "Default")
      (node (ref "J1") (pin "S2") (pinfunction "DETECTION_2_S2") (pintype "bidirectional"))
    )
    (net (code "66") (name "unconnected-(J2-PadA8)") (class "Default")
      (node (ref "J2") (pin "A8") (pinfunction "A8_A8") (pintype "bidirectional"))
    )
    (net (code "67") (name "unconnected-(J2-PadB8)") (class "Default")
      (node (ref "J2") (pin "B8") (pinfunction "B8_B8") (pintype "bidirectional"))
    )
    (net (code "68") (name "unconnected-(J3-Pad1)") (class "Default")
      (node (ref "J3") (pin "1") (pinfunction "1_1") (pintype "bidirectional"))
    )
    (net (code "69") (name "unconnected-(J3-Pad6)") (class "Default")
      (node (ref "J3") (pin "6") (pinfunction "6_6") (pintype "bidirectional"))
    )
    (net (code "70") (name "unconnected-(J3-Pad7)") (class "Default")
      (node (ref "J3") (pin "7") (pinfunction "7_7") (pintype "bidirectional"))
    )
    (net (code "71") (name "unconnected-(U2-NC-Pad22)") (class "Default")
      (node (ref "U2") (pin "22") (pinfunction "NC_22") (pintype "no_connect"))
    )
    (net (code "72") (name "unconnected-(U4-~{ALERT}-Pad5)") (class "Default")
      (node (ref "U4") (pin "5") (pinfunction "~{ALERT}_5") (pintype "output"))
    )
  )
)
